# voltage_ref.net
KiCad netlist of a schematic drawn in Altium Designer
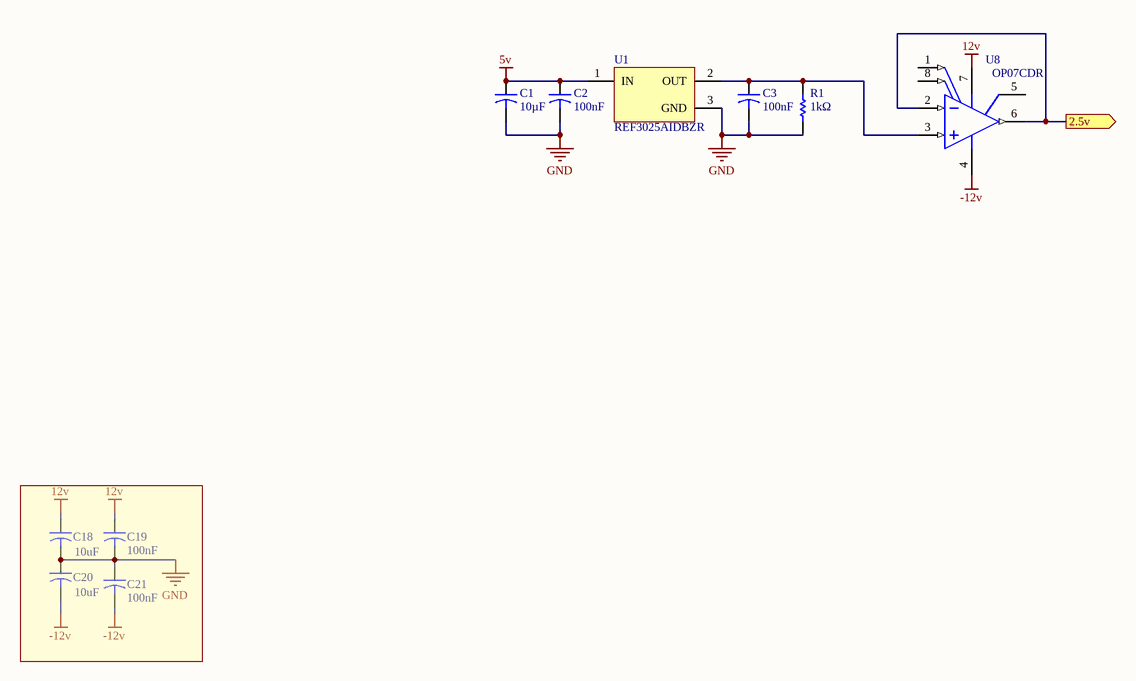
[diagram p0: voltage_ref.SchDoc]

(export (version "E")
  (design (tool "Eeschema 10.0.6"))
  (components
    (comp (ref "C1")
      (value "~")
      (footprint "Passives:CAP 1206/3216")
      (description "Capacitor")
      (fields
        (field (name "MANUFACTURER") "SAMSUNG")
        (field (name "MANUFACTURER PART NUMBER") "CL31A106KAHNNNE")
        (field (name "CAPACITANCE") "10µF")
        (field (name "PUBLISHER") "Altium Limited")
      )
      (libsource (lib "Miscellaneous Devices") (part "Cap2"))
    )
    (comp (ref "C2")
      (value "~")
      (footprint "Passives:CAP 0805/2012")
      (description "Capacitor")
      (fields
        (field (name "CAPACITANCE") "100nF")
        (field (name "MANUFACTURER") "YAGEO")
        (field (name "MANUFACTURER PART NUMBER") "CC0805JRX7R9BB104")
      )
      (libsource (lib "Miscellaneous Devices") (part "Cap2"))
    )
    (comp (ref "C3")
      (value "~")
      (footprint "Passives:CAP 0805/2012")
      (description "Capacitor")
      (fields
        (field (name "CAPACITANCE") "100nF")
        (field (name "MANUFACTURER") "YAGEO")
        (field (name "MANUFACTURER PART NUMBER") "CC0805JRX7R9BB104")
      )
      (libsource (lib "Miscellaneous Devices") (part "Cap2"))
    )
    (comp (ref "C18")
      (value "10uF")
      (footprint "Passives:CAP 1206/3216")
      (description "Capacitor")
      (fields
        (field (name "MANUFACTURER") "SAMSUNG")
        (field (name "MANUFACTURER PART NUMBER") "CL31A106KAHNNNE")
        (field (name "PUBLISHER") "Altium Limited")
      )
      (libsource (lib "Miscellaneous Devices") (part "Cap2"))
    )
    (comp (ref "C19")
      (value "~")
      (footprint "Passives:CAP 0805/2012")
      (description "Capacitor")
      (fields
        (field (name "CAPACITANCE") "100nF")
        (field (name "MANUFACTURER") "YAGEO")
        (field (name "MANUFACTURER PART NUMBER") "CC0805JRX7R9BB104")
      )
      (libsource (lib "Miscellaneous Devices") (part "Cap2"))
    )
    (comp (ref "C20")
      (value "10uF")
      (footprint "Passives:CAP 1206/3216")
      (description "Capacitor")
      (fields
        (field (name "MANUFACTURER") "SAMSUNG")
        (field (name "MANUFACTURER PART NUMBER") "CL31A106KAHNNNE")
        (field (name "PUBLISHER") "Altium Limited")
      )
      (libsource (lib "Miscellaneous Devices") (part "Cap2"))
    )
    (comp (ref "C21")
      (value "~")
      (footprint "Passives:CAP 0805/2012")
      (description "Capacitor")
      (fields
        (field (name "CAPACITANCE") "100nF")
        (field (name "MANUFACTURER") "YAGEO")
        (field (name "MANUFACTURER PART NUMBER") "CC0805JRX7R9BB104")
      )
      (libsource (lib "Miscellaneous Devices") (part "Cap2"))
    )
    (comp (ref "R1")
      (value "~")
      (footprint "Passives:RES 0805/2012")
      (description "Resistor")
      (fields
        (field (name "MANUFACTURER") "VIKING")
        (field (name "MANUFACTURER PART NUMBER") "AR05BTCW1001")
        (field (name "RESISTANCE") "1kΩ")
        (field (name "PUBLISHER") "Altium Limited")
      )
      (libsource (lib "Miscellaneous Devices") (part "Res1"))
    )
    (comp (ref "U1")
      (value "~")
      (footprint "TI-DBZ3_N")
      (description "Voltage reference, 2.5V")
      (fields
        (field (name "MANUFACTURER") "Texas Instruments")
        (field (name "MANUFACTURER PART NUMBER") "REF3025AIDBZR")
      )
      (libsource (lib "TI Power Management Series Voltage Reference") (part "REF3025AIDBZR"))
    )
    (comp (ref "U8")
      (value "~")
      (footprint "TI-D8_N")
      (fields
        (field (name "SUPPLIER PART NUMBER 1") "OP07CDR")
        (field (name "MANUFACTURER") "TEXAS INSTRUMENTS")
        (field (name "MANUFACTURER PART NUMBER") "OP07CDR")
      )
      (libsource (lib "TI Amplifiers and Linear Operational Amplifier General Purpose") (part "OP07CDR"))
    )
  )
  (nets
    (net (code "1") (name "-12v") (class "Default")
      (node (ref "C20") (pin "2") (pinfunction "2_2") (pintype "passive"))
      (node (ref "C21") (pin "2") (pinfunction "2_2") (pintype "passive"))
      (node (ref "U8") (pin "4") (pinfunction "VCC-_4") (pintype "power_in"))
    )
    (net (code "2") (name "/2.5v") (class "Default")
      (node (ref "U8") (pin "2") (pinfunction "IN-_2") (pintype "input"))
      (node (ref "U8") (pin "6") (pinfunction "OUT_6") (pintype "output"))
    )
    (net (code "3") (name "5v") (class "Default")
      (node (ref "C1") (pin "1") (pinfunction "1_1") (pintype "passive"))
      (node (ref "C2") (pin "1") (pinfunction "1_1") (pintype "passive"))
      (node (ref "U1") (pin "1") (pinfunction "IN_1") (pintype "power_in"))
    )
    (net (code "4") (name "12v") (class "Default")
      (node (ref "C18") (pin "1") (pinfunction "1_1") (pintype "passive"))
      (node (ref "C19") (pin "1") (pinfunction "1_1") (pintype "passive"))
      (node (ref "U8") (pin "7") (pinfunction "VCC+_7") (pintype "power_in"))
    )
    (net (code "5") (name "GND") (class "Default")
      (node (ref "C1") (pin "2") (pinfunction "2_2") (pintype "passive"))
      (node (ref "C18") (pin "2") (pinfunction "2_2") (pintype "passive"))
      (node (ref "C19") (pin "2") (pinfunction "2_2") (pintype "passive"))
      (node (ref "C2") (pin "2") (pinfunction "2_2") (pintype "passive"))
      (node (ref "C20") (pin "1") (pinfunction "1_1") (pintype "passive"))
      (node (ref "C21") (pin "1") (pinfunction "1_1") (pintype "passive"))
      (node (ref "C3") (pin "2") (pinfunction "2_2") (pintype "passive"))
      (node (ref "R1") (pin "2") (pinfunction "2_2") (pintype "passive"))
      (node (ref "U1") (pin "3") (pinfunction "GND_3") (pintype "power_in"))
    )
    (net (code "6") (name "Net-(U1-OUT)") (class "Default")
      (node (ref "C3") (pin "1") (pinfunction "1_1") (pintype "passive"))
      (node (ref "R1") (pin "1") (pinfunction "1_1") (pintype "passive"))
      (node (ref "U1") (pin "2") (pinfunction "OUT_2") (pintype "power_in"))
      (node (ref "U8") (pin "3") (pinfunction "IN+_3") (pintype "input"))
    )
    (net (code "7") (name "unconnected-(U8-NC-Pad5)") (class "Default")
      (node (ref "U8") (pin "5") (pinfunction "NC_5") (pintype "passive"))
    )
    (net (code "8") (name "unconnected-(U8-OFFSET_N1-Pad1)") (class "Default")
      (node (ref "U8") (pin "1") (pinfunction "OFFSET_N1_1") (pintype "input"))
    )
    (net (code "9") (name "unconnected-(U8-OFFSET_N2-Pad8)") (class "Default")
      (node (ref "U8") (pin "8") (pinfunction "OFFSET_N2_8") (pintype "input"))
    )
  )
)
